# Sheet_MCU_IO.net
KiCad netlist of a schematic drawn in Altium Designer
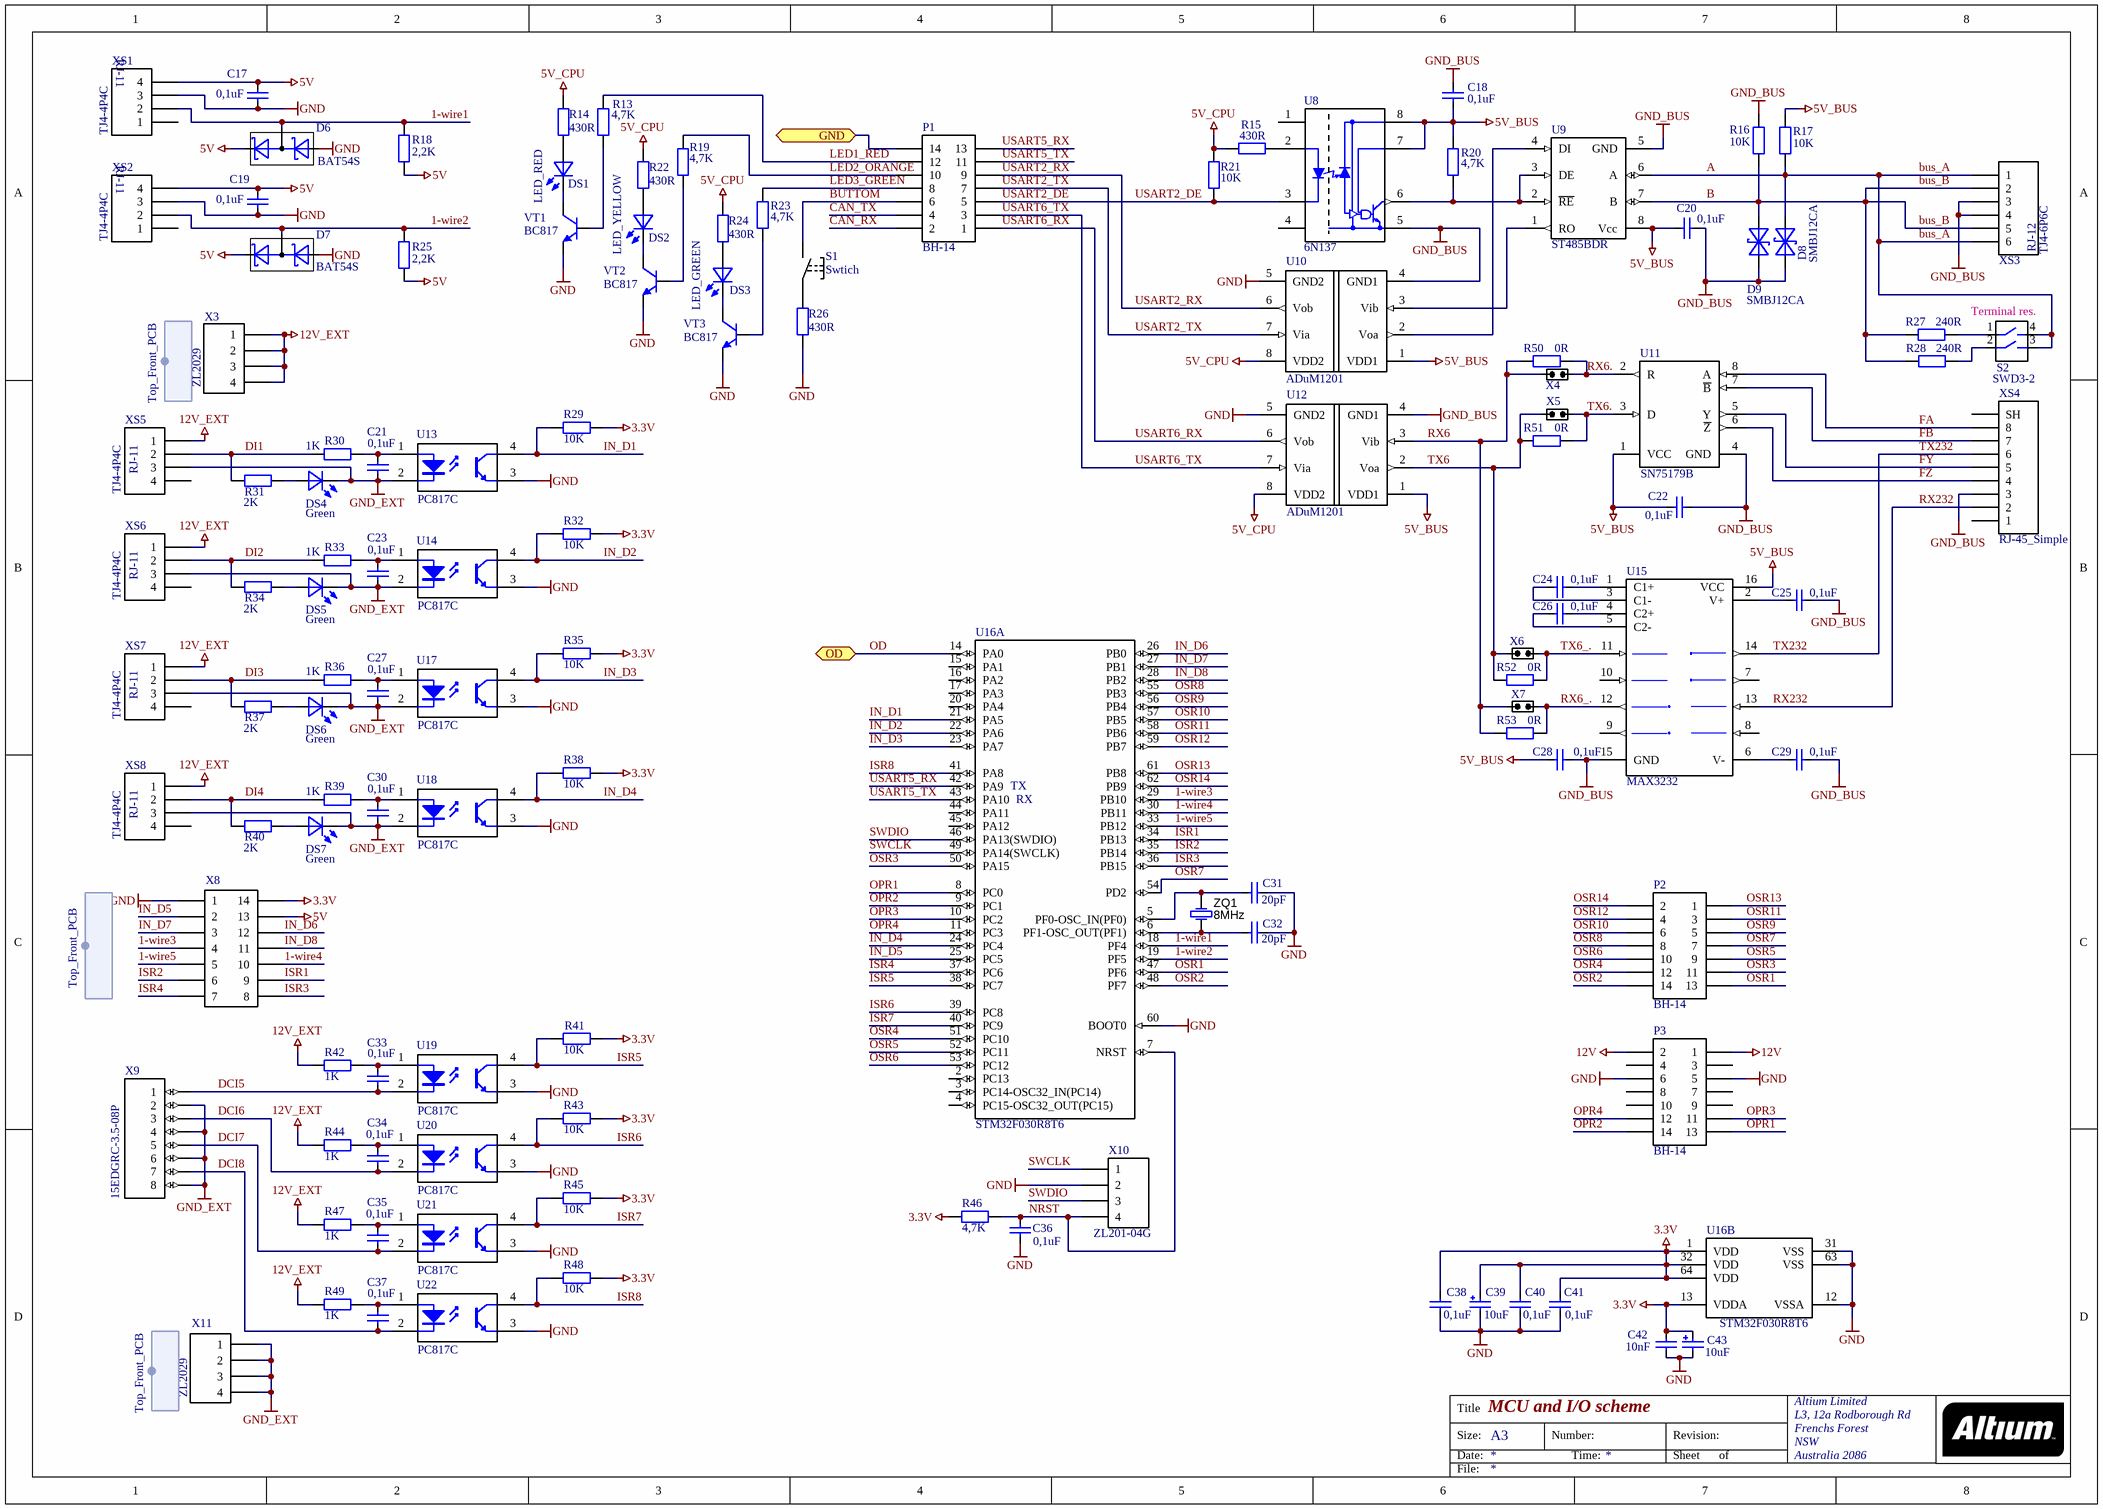
[diagram p0: Sheet_MCU_IO.SchDoc]

(export (version "E")
  (design (tool "Eeschema 10.0.6"))
  (components
    (comp (ref "C17")
      (value "0,1uF")
      (footprint "C_0805")
      (description "Capacitor semi")
      (fields (field (name "Comment") "Cap_Semi"))
      (libsource (lib "Capacitor") (part "Cap_Semi"))
    )
    (comp (ref "C18")
      (value "0,1uF")
      (footprint "C_0805")
      (description "Capacitor semi")
      (fields (field (name "Comment") "Cap_Semi"))
      (libsource (lib "Capacitor") (part "Cap_Semi"))
    )
    (comp (ref "C19")
      (value "0,1uF")
      (footprint "C_0805")
      (description "Capacitor semi")
      (fields (field (name "Comment") "Cap_Semi"))
      (libsource (lib "Capacitor") (part "Cap_Semi"))
    )
    (comp (ref "C20")
      (value "0,1uF")
      (footprint "C_0805")
      (description "Capacitor semi")
      (fields (field (name "Comment") "Cap_Semi"))
      (libsource (lib "Capacitor") (part "Cap_Semi"))
    )
    (comp (ref "C21")
      (value "0,1uF")
      (footprint "C_0805")
      (description "Capacitor semi")
      (fields (field (name "Comment") "Cap_Semi"))
      (libsource (lib "Capacitor") (part "Cap_Semi"))
    )
    (comp (ref "C22")
      (value "0,1uF")
      (footprint "C_0805")
      (description "Capacitor semi")
      (fields (field (name "Comment") "Cap_Semi"))
      (libsource (lib "Capacitor") (part "Cap_Semi"))
    )
    (comp (ref "C23")
      (value "0,1uF")
      (footprint "C_0805")
      (description "Capacitor semi")
      (fields (field (name "Comment") "Cap_Semi"))
      (libsource (lib "Capacitor") (part "Cap_Semi"))
    )
    (comp (ref "C24")
      (value "0,1uF")
      (footprint "C_0805")
      (description "Capacitor semi")
      (fields (field (name "Comment") "Cap_Semi"))
      (libsource (lib "Capacitor") (part "Cap_Semi"))
    )
    (comp (ref "C25")
      (value "0,1uF")
      (footprint "C_0805")
      (description "Capacitor semi")
      (fields (field (name "Comment") "Cap_Semi"))
      (libsource (lib "Capacitor") (part "Cap_Semi"))
    )
    (comp (ref "C26")
      (value "0,1uF")
      (footprint "C_0805")
      (description "Capacitor semi")
      (fields (field (name "Comment") "Cap_Semi"))
      (libsource (lib "Capacitor") (part "Cap_Semi"))
    )
    (comp (ref "C27")
      (value "0,1uF")
      (footprint "C_0805")
      (description "Capacitor semi")
      (fields (field (name "Comment") "Cap_Semi"))
      (libsource (lib "Capacitor") (part "Cap_Semi"))
    )
    (comp (ref "C28")
      (value "0,1uF")
      (footprint "C_0805")
      (description "Capacitor semi")
      (fields (field (name "Comment") "Cap_Semi"))
      (libsource (lib "Capacitor") (part "Cap_Semi"))
    )
    (comp (ref "C29")
      (value "0,1uF")
      (footprint "C_0805")
      (description "Capacitor semi")
      (fields (field (name "Comment") "Cap_Semi"))
      (libsource (lib "Capacitor") (part "Cap_Semi"))
    )
    (comp (ref "C30")
      (value "0,1uF")
      (footprint "C_0805")
      (description "Capacitor semi")
      (fields (field (name "Comment") "Cap_Semi"))
      (libsource (lib "Capacitor") (part "Cap_Semi"))
    )
    (comp (ref "C31")
      (value "20pF")
      (footprint "C_0805")
      (description "Capacitor semi")
      (fields (field (name "Comment") "Cap_Semi"))
      (libsource (lib "Capacitor") (part "Cap_Semi"))
    )
    (comp (ref "C32")
      (value "20pF")
      (footprint "C_0805")
      (description "Capacitor semi")
      (fields (field (name "Comment") "Cap_Semi"))
      (libsource (lib "Capacitor") (part "Cap_Semi"))
    )
    (comp (ref "C33")
      (value "0,1uF")
      (footprint "C_0805")
      (description "Capacitor semi")
      (fields (field (name "Comment") "Cap_Semi"))
      (libsource (lib "Capacitor") (part "Cap_Semi"))
    )
    (comp (ref "C34")
      (value "0,1uF")
      (footprint "C_0805")
      (description "Capacitor semi")
      (fields (field (name "Comment") "Cap_Semi"))
      (libsource (lib "Capacitor") (part "Cap_Semi"))
    )
    (comp (ref "C35")
      (value "0,1uF")
      (footprint "C_0805")
      (description "Capacitor semi")
      (fields (field (name "Comment") "Cap_Semi"))
      (libsource (lib "Capacitor") (part "Cap_Semi"))
    )
    (comp (ref "C36")
      (value "0,1uF")
      (footprint "C_0805")
      (description "Capacitor semi")
      (fields (field (name "Comment") "Cap_Semi"))
      (libsource (lib "Capacitor") (part "Cap_Semi"))
    )
    (comp (ref "C37")
      (value "0,1uF")
      (footprint "C_0805")
      (description "Capacitor semi")
      (fields (field (name "Comment") "Cap_Semi"))
      (libsource (lib "Capacitor") (part "Cap_Semi"))
    )
    (comp (ref "C38")
      (value "0,1uF")
      (footprint "C_0805")
      (description "Capacitor semi")
      (fields (field (name "Comment") "Cap_Semi"))
      (libsource (lib "Capacitor") (part "Cap_Semi"))
    )
    (comp (ref "C39")
      (value "10uF")
      (footprint "5x11")
      (description "Capacitor polar")
      (fields (field (name "Comment") "Cap_Polar"))
      (libsource (lib "Capacitor") (part "Capacitor Polar"))
    )
    (comp (ref "C40")
      (value "0,1uF")
      (footprint "C_0805")
      (description "Capacitor semi")
      (fields (field (name "Comment") "Cap_Semi"))
      (libsource (lib "Capacitor") (part "Cap_Semi"))
    )
    (comp (ref "C41")
      (value "0,1uF")
      (footprint "C_0805")
      (description "Capacitor semi")
      (fields (field (name "Comment") "Cap_Semi"))
      (libsource (lib "Capacitor") (part "Cap_Semi"))
    )
    (comp (ref "C42")
      (value "10nF")
      (footprint "C_0805")
      (description "Capacitor semi")
      (fields (field (name "Comment") "Cap_Semi"))
      (libsource (lib "Capacitor") (part "Cap_Semi"))
    )
    (comp (ref "C43")
      (value "10uF")
      (footprint "5x11")
      (description "Capacitor polar")
      (fields (field (name "Comment") "Cap_Polar"))
      (libsource (lib "Capacitor") (part "Capacitor Polar"))
    )
    (comp (ref "D6")
      (value "BAT54S")
      (footprint "SOT-23_d")
      (description "Diode Schottky")
      (libsource (lib "Diode") (part "BAT54S"))
    )
    (comp (ref "D7")
      (value "BAT54S")
      (footprint "SOT-23_d")
      (description "Diode Schottky")
      (libsource (lib "Diode") (part "BAT54S"))
    )
    (comp (ref "D8")
      (value "SMBJ12CA")
      (footprint "SMB")
      (description "Supressor")
      (libsource (lib "Diode") (part "SMBJ12CA"))
    )
    (comp (ref "D9")
      (value "SMBJ12CA")
      (footprint "SMB")
      (description "Supressor")
      (libsource (lib "Diode") (part "SMBJ12CA"))
    )
    (comp (ref "DS1")
      (value "LED_RED")
      (footprint "LED_RED")
      (description "LED")
      (libsource (lib "LEDs") (part "LED_RED"))
    )
    (comp (ref "DS2")
      (value "LED_YELLOW")
      (footprint "LED_YELLOW")
      (description "LED")
      (libsource (lib "LEDs") (part "LED_YELLOW"))
    )
    (comp (ref "DS3")
      (value "LED_GREEN")
      (footprint "LED_GREEN")
      (description "LED")
      (libsource (lib "LEDs") (part "LED_GREEN"))
    )
    (comp (ref "DS4")
      (value "Green")
      (footprint "LED_SMD_0805")
      (description "LED_SMD")
      (libsource (lib "LEDs") (part "LED"))
    )
    (comp (ref "DS5")
      (value "Green")
      (footprint "LED_SMD_0805")
      (description "LED_SMD")
      (libsource (lib "LEDs") (part "LED"))
    )
    (comp (ref "DS6")
      (value "Green")
      (footprint "LED_SMD_0805")
      (description "LED_SMD")
      (libsource (lib "LEDs") (part "LED"))
    )
    (comp (ref "DS7")
      (value "Green")
      (footprint "LED_SMD_0805")
      (description "LED_SMD")
      (libsource (lib "LEDs") (part "LED"))
    )
    (comp (ref "P1")
      (value "BH-14")
      (footprint "BH-14")
      (description "IDC/BH")
      (fields (field (name "PUBLISHER") "Altium Limited"))
      (libsource (lib "") (part "BH-14_1"))
    )
    (comp (ref "P2")
      (value "BH-14")
      (footprint "BH-14")
      (description "IDC/BH")
      (fields (field (name "PUBLISHER") "Altium Limited"))
      (libsource (lib "Connect") (part "BH-14"))
    )
    (comp (ref "P3")
      (value "BH-14")
      (footprint "BH-14")
      (description "IDC/BH")
      (fields (field (name "PUBLISHER") "Altium Limited"))
      (libsource (lib "Connect") (part "BH-14"))
    )
    (comp (ref "R13")
      (value "4,7K")
      (footprint "R_0805")
      (description "Resistor")
      (libsource (lib "Resistors") (part "Resistor"))
    )
    (comp (ref "R14")
      (value "430R")
      (footprint "R_0805")
      (description "Resistor")
      (libsource (lib "") (part "Resistor_3"))
    )
    (comp (ref "R15")
      (value "430R")
      (footprint "R_0805")
      (description "Resistor")
      (libsource (lib "") (part "Resistor_2"))
    )
    (comp (ref "R16")
      (value "10K")
      (footprint "R_0805")
      (description "Resistor")
      (libsource (lib "Resistors") (part "Resistor"))
    )
    (comp (ref "R17")
      (value "10K")
      (footprint "R_0805")
      (description "Resistor")
      (libsource (lib "Resistors") (part "Resistor"))
    )
    (comp (ref "R18")
      (value "2,2K")
      (footprint "R_0805")
      (description "Resistor")
      (libsource (lib "") (part "Resistor_2"))
    )
    (comp (ref "R19")
      (value "4,7K")
      (footprint "R_0805")
      (description "Resistor")
      (libsource (lib "Resistors") (part "Resistor"))
    )
    (comp (ref "R20")
      (value "4,7K")
      (footprint "R_0805")
      (description "Resistor")
      (libsource (lib "Resistors") (part "Resistor"))
    )
    (comp (ref "R21")
      (value "10K")
      (footprint "R_0805")
      (description "Resistor")
      (libsource (lib "Resistors") (part "Resistor"))
    )
    (comp (ref "R22")
      (value "430R")
      (footprint "R_0805")
      (description "Resistor")
      (libsource (lib "") (part "Resistor_3"))
    )
    (comp (ref "R23")
      (value "4,7K")
      (footprint "R_0805")
      (description "Resistor")
      (libsource (lib "Resistors") (part "Resistor"))
    )
    (comp (ref "R24")
      (value "430R")
      (footprint "R_0805")
      (description "Resistor")
      (libsource (lib "") (part "Resistor_3"))
    )
    (comp (ref "R25")
      (value "2,2K")
      (footprint "R_0805")
      (description "Resistor")
      (libsource (lib "") (part "Resistor_2"))
    )
    (comp (ref "R26")
      (value "430R")
      (footprint "R_0805")
      (description "Resistor")
      (libsource (lib "") (part "Resistor_3"))
    )
    (comp (ref "R27")
      (value "240R")
      (footprint "R_1206")
      (description "Resistor")
      (libsource (lib "") (part "Resistor_1"))
    )
    (comp (ref "R28")
      (value "240R")
      (footprint "R_1206")
      (description "Resistor")
      (libsource (lib "") (part "Resistor_1"))
    )
    (comp (ref "R29")
      (value "10K")
      (footprint "R_0805")
      (description "Resistor")
      (libsource (lib "") (part "Resistor_2"))
    )
    (comp (ref "R30")
      (value "1K")
      (footprint "R_0805")
      (description "Resistor")
      (libsource (lib "") (part "Resistor_2"))
    )
    (comp (ref "R31")
      (value "2K")
      (footprint "R_0805")
      (description "Resistor")
      (libsource (lib "") (part "Resistor_2"))
    )
    (comp (ref "R32")
      (value "10K")
      (footprint "R_0805")
      (description "Resistor")
      (libsource (lib "") (part "Resistor_2"))
    )
    (comp (ref "R33")
      (value "1K")
      (footprint "R_0805")
      (description "Resistor")
      (libsource (lib "") (part "Resistor_2"))
    )
    (comp (ref "R34")
      (value "2K")
      (footprint "R_0805")
      (description "Resistor")
      (libsource (lib "") (part "Resistor_2"))
    )
    (comp (ref "R35")
      (value "10K")
      (footprint "R_0805")
      (description "Resistor")
      (libsource (lib "") (part "Resistor_2"))
    )
    (comp (ref "R36")
      (value "1K")
      (footprint "R_0805")
      (description "Resistor")
      (libsource (lib "") (part "Resistor_2"))
    )
    (comp (ref "R37")
      (value "2K")
      (footprint "R_0805")
      (description "Resistor")
      (libsource (lib "") (part "Resistor_2"))
    )
    (comp (ref "R38")
      (value "10K")
      (footprint "R_0805")
      (description "Resistor")
      (libsource (lib "") (part "Resistor_2"))
    )
    (comp (ref "R39")
      (value "1K")
      (footprint "R_0805")
      (description "Resistor")
      (libsource (lib "") (part "Resistor_2"))
    )
    (comp (ref "R40")
      (value "2K")
      (footprint "R_0805")
      (description "Resistor")
      (libsource (lib "") (part "Resistor_2"))
    )
    (comp (ref "R41")
      (value "10K")
      (footprint "R_0805")
      (description "Resistor")
      (libsource (lib "") (part "Resistor_2"))
    )
    (comp (ref "R42")
      (value "1K")
      (footprint "R_0805")
      (description "Resistor")
      (libsource (lib "") (part "Resistor_2"))
    )
    (comp (ref "R43")
      (value "10K")
      (footprint "R_0805")
      (description "Resistor")
      (libsource (lib "") (part "Resistor_2"))
    )
    (comp (ref "R44")
      (value "1K")
      (footprint "R_0805")
      (description "Resistor")
      (libsource (lib "") (part "Resistor_2"))
    )
    (comp (ref "R45")
      (value "10K")
      (footprint "R_0805")
      (description "Resistor")
      (libsource (lib "") (part "Resistor_2"))
    )
    (comp (ref "R46")
      (value "4,7K")
      (footprint "R_0805")
      (description "Resistor")
      (libsource (lib "") (part "Resistor_1"))
    )
    (comp (ref "R47")
      (value "1K")
      (footprint "R_0805")
      (description "Resistor")
      (libsource (lib "") (part "Resistor_2"))
    )
    (comp (ref "R48")
      (value "10K")
      (footprint "R_0805")
      (description "Resistor")
      (libsource (lib "") (part "Resistor_2"))
    )
    (comp (ref "R49")
      (value "1K")
      (footprint "R_0805")
      (description "Resistor")
      (libsource (lib "") (part "Resistor_2"))
    )
    (comp (ref "R50")
      (value "0R")
      (footprint "R_0805")
      (description "Resistor")
      (libsource (lib "") (part "Resistor_2"))
    )
    (comp (ref "R51")
      (value "0R")
      (footprint "R_0805")
      (description "Resistor")
      (libsource (lib "") (part "Resistor_2"))
    )
    (comp (ref "R52")
      (value "0R")
      (footprint "R_0805")
      (description "Resistor")
      (libsource (lib "") (part "Resistor_2"))
    )
    (comp (ref "R53")
      (value "0R")
      (footprint "R_0805")
      (description "Resistor")
      (libsource (lib "") (part "Resistor_2"))
    )
    (comp (ref "S1")
      (value "Swtich")
      (footprint "Swich_TACTA-68N-F_")
      (libsource (lib "Other") (part "Swtich"))
    )
    (comp (ref "S2")
      (value "SW DIP-2")
      (footprint "Swich_DIP2")
      (description "DIP Switch_2")
      (fields (field (name "ALTIUM_UNNAMED_1") "SWD3-2"))
      (libsource (lib "Other") (part "SW DIP-2"))
    )
    (comp (ref "U8")
      (value "6N137")
      (footprint "DIP-8")
      (description "Optocoupler")
      (libsource (lib "Chip_Packaging") (part "6N137"))
    )
    (comp (ref "U9")
      (value "ST485BDR")
      (footprint "SO-8_N")
      (description "RS-485/RS-422 Transceiver")
      (libsource (lib "Chip_Packaging") (part "ST485BDR"))
    )
    (comp (ref "U10")
      (value "ADuM1201")
      (footprint "SO-8_N")
      (description "Dual-Channel Digital Isolators")
      (libsource (lib "Chip_Packaging") (part "ADuM1201"))
    )
    (comp (ref "U11")
      (value "SN75179B")
      (footprint "SO-8_L")
      (description "RS485/RS422 Differential driver and receiver pair")
      (libsource (lib "Chip_Packaging") (part "SN75179B"))
    )
    (comp (ref "U12")
      (value "ADuM1201")
      (footprint "SO-8_N")
      (description "Dual-Channel Digital Isolators")
      (libsource (lib "Chip_Packaging") (part "ADuM1201"))
    )
    (comp (ref "U13")
      (value "PC817C")
      (footprint "DIP-4")
      (description "Optocoupler")
      (libsource (lib "Chip_Packaging") (part "PC817"))
    )
    (comp (ref "U14")
      (value "PC817C")
      (footprint "DIP-4")
      (description "Optocoupler")
      (libsource (lib "Chip_Packaging") (part "PC817"))
    )
    (comp (ref "U15")
      (value "MAX3232")
      (footprint "SO-16_N")
      (description "RS-232 Transceiver")
      (fields (field (name "PUBLISHER") "Altium Limited"))
      (libsource (lib "Chip_Packaging") (part "MAX3232"))
    )
    (comp (ref "U16")
      (value "STM32F030R8T6")
      (footprint "LQFP64_L")
      (libsource (lib "Chip_Packaging") (part "STM32F030R8T6"))
    )
    (comp (ref "U17")
      (value "PC817C")
      (footprint "DIP-4")
      (description "Optocoupler")
      (libsource (lib "Chip_Packaging") (part "PC817"))
    )
    (comp (ref "U18")
      (value "PC817C")
      (footprint "DIP-4")
      (description "Optocoupler")
      (libsource (lib "Chip_Packaging") (part "PC817"))
    )
    (comp (ref "U19")
      (value "PC817C")
      (footprint "DIP-4")
      (description "Optocoupler")
      (libsource (lib "Chip_Packaging") (part "PC817"))
    )
    (comp (ref "U20")
      (value "PC817C")
      (footprint "DIP-4")
      (description "Optocoupler")
      (libsource (lib "Chip_Packaging") (part "PC817"))
    )
    (comp (ref "U21")
      (value "PC817C")
      (footprint "DIP-4")
      (description "Optocoupler")
      (libsource (lib "Chip_Packaging") (part "PC817"))
    )
    (comp (ref "U22")
      (value "PC817C")
      (footprint "DIP-4")
      (description "Optocoupler")
      (libsource (lib "Chip_Packaging") (part "PC817"))
    )
    (comp (ref "VT1")
      (value "BC817")
      (footprint "SOT-23_N")
      (description "NPN")
      (libsource (lib "Transistors") (part "BC817"))
    )
    (comp (ref "VT2")
      (value "BC817")
      (footprint "SOT-23_N")
      (description "NPN")
      (libsource (lib "Transistors") (part "BC817"))
    )
    (comp (ref "VT3")
      (value "BC817")
      (footprint "SOT-23_N")
      (description "NPN")
      (libsource (lib "Transistors") (part "BC817"))
    )
    (comp (ref "X3")
      (value "ZL2029")
      (footprint "PLS-4-3D")
      (description "Header, 4-Pin")
      (fields (field (name "ALTIUM_UNNAMED_1") "ZL2029") (field (name "PUBLISHER") "Altium Limited"))
      (libsource (lib "Connect") (part "PLS-4"))
    )
    (comp (ref "X4")
      (value "JMP")
      (footprint "PLS-2-2")
      (description "Jumper")
      (fields (field (name "PUBLISHER") "Altium Limited"))
      (libsource (lib "Connect") (part "JMP"))
    )
    (comp (ref "X5")
      (value "JMP")
      (footprint "PLS-2-2")
      (description "Jumper")
      (fields (field (name "PUBLISHER") "Altium Limited"))
      (libsource (lib "Connect") (part "JMP"))
    )
    (comp (ref "X6")
      (value "JMP")
      (footprint "PLS-2-2")
      (description "Jumper")
      (fields (field (name "PUBLISHER") "Altium Limited"))
      (libsource (lib "Connect") (part "JMP"))
    )
    (comp (ref "X7")
      (value "JMP")
      (footprint "PLS-2-2")
      (description "Jumper")
      (fields (field (name "PUBLISHER") "Altium Limited"))
      (libsource (lib "Connect") (part "JMP"))
    )
    (comp (ref "X8")
      (value "PLS2-14")
      (footprint "PLS2-14")
      (description "Header, 14-Pin")
      (libsource (lib "Connect") (part "PLS2-14"))
    )
    (comp (ref "X9")
      (value "15EDGRC-3.5-08P")
      (footprint "MC_3.5_8")
      (description "Connector 3.5mm")
      (libsource (lib "Connect") (part "MC_3.5_8"))
    )
    (comp (ref "X10")
      (value "PLS-4")
      (footprint "PLS-4-3D")
      (description "ZL201-04G")
      (fields (field (name "ALTIUM_UNNAMED_1") "ZL201-04G") (field (name "PUBLISHER") "Altium Limited"))
      (libsource (lib "") (part "PLS-4_1"))
    )
    (comp (ref "X11")
      (value "PLS-4")
      (footprint "PLS-4-3D")
      (description "ZL2029")
      (fields (field (name "ALTIUM_UNNAMED_1") "ZL2029") (field (name "PUBLISHER") "Altium Limited"))
      (libsource (lib "Connect") (part "PLS-4"))
    )
    (comp (ref "XS1")
      (value "RJ-11")
      (footprint "RJ-11 - TJ4-4P4C")
      (description "TJ4-4P4C")
      (fields (field (name "ALTIUM_UNNAMED_1") "TJ4-4P4C"))
      (libsource (lib "Connect") (part "RJ-11"))
    )
    (comp (ref "XS2")
      (value "RJ-11")
      (footprint "RJ-11 - TJ4-4P4C")
      (description "TJ4-4P4C")
      (fields (field (name "ALTIUM_UNNAMED_1") "TJ4-4P4C"))
      (libsource (lib "Connect") (part "RJ-11"))
    )
    (comp (ref "XS3")
      (value "RJ-12")
      (footprint "RJ-12 - TJ4-6P6C")
      (description "TJ4-6P6C")
      (fields (field (name "ALTIUM_UNNAMED_1") "TJ4-6P6C"))
      (libsource (lib "Connect") (part "RJ-12"))
    )
    (comp (ref "XS4")
      (value "RJ-45_Simple")
      (footprint "RJ-45 - TJ4-8P8C")
      (description "Connector RJ-45 Simple")
      (libsource (lib "Connect") (part "RJ-45_Simple"))
    )
    (comp (ref "XS5")
      (value "RJ-11")
      (footprint "RJ-11 - TJ4-4P4C")
      (description "TJ4-4P4C")
      (fields (field (name "ALTIUM_UNNAMED_1") "TJ4-4P4C"))
      (libsource (lib "") (part "RJ-11_1"))
    )
    (comp (ref "XS6")
      (value "RJ-11")
      (footprint "RJ-11 - TJ4-4P4C")
      (description "TJ4-4P4C")
      (fields (field (name "ALTIUM_UNNAMED_1") "TJ4-4P4C"))
      (libsource (lib "") (part "RJ-11_1"))
    )
    (comp (ref "XS7")
      (value "RJ-11")
      (footprint "RJ-11 - TJ4-4P4C")
      (description "TJ4-4P4C")
      (fields (field (name "ALTIUM_UNNAMED_1") "TJ4-4P4C"))
      (libsource (lib "") (part "RJ-11_1"))
    )
    (comp (ref "XS8")
      (value "RJ-11")
      (footprint "RJ-11 - TJ4-4P4C")
      (description "TJ4-4P4C")
      (fields (field (name "ALTIUM_UNNAMED_1") "TJ4-4P4C"))
      (libsource (lib "") (part "RJ-11_1"))
    )
    (comp (ref "ZQ1")
      (value "8MHz")
      (footprint "HC49S_3D")
      (description "Crystal Oscillator")
      (fields (field (name "PUBLISHER") "Altium Limited"))
      (libsource (lib "Oscillator") (part "XTAL"))
    )
  )
  (nets
    (net (code "1") (name "/1-wire1") (class "Default")
      (node (ref "D6") (pin "3") (pinfunction "CA_3") (pintype "passive"))
      (node (ref "R18") (pin "1") (pinfunction "1_1") (pintype "passive"))
      (node (ref "U16") (pin "18") (pinfunction "PF4_18") (pintype "bidirectional"))
      (node (ref "XS1") (pin "2") (pinfunction "2_2") (pintype "passive"))
    )
    (net (code "2") (name "/1-wire2") (class "Default")
      (node (ref "D7") (pin "3") (pinfunction "CA_3") (pintype "passive"))
      (node (ref "R25") (pin "1") (pinfunction "1_1") (pintype "passive"))
      (node (ref "U16") (pin "19") (pinfunction "PF5_19") (pintype "bidirectional"))
      (node (ref "XS2") (pin "2") (pinfunction "2_2") (pintype "passive"))
    )
    (net (code "3") (name "/1-wire3") (class "Default")
      (node (ref "U16") (pin "29") (pinfunction "PB10_29") (pintype "bidirectional"))
      (node (ref "X8") (pin "4") (pinfunction "4_4") (pintype "passive"))
    )
    (net (code "4") (name "/1-wire4") (class "Default")
      (node (ref "U16") (pin "30") (pinfunction "PB11_30") (pintype "bidirectional"))
      (node (ref "X8") (pin "10") (pinfunction "10_10") (pintype "passive"))
    )
    (net (code "5") (name "/1-wire5") (class "Default")
      (node (ref "U16") (pin "33") (pinfunction "PB12_33") (pintype "bidirectional"))
      (node (ref "X8") (pin "5") (pinfunction "5_5") (pintype "passive"))
    )
    (net (code "6") (name "/A") (class "Default")
      (node (ref "D8") (pin "2") (pinfunction "C_2") (pintype "passive"))
      (node (ref "R17") (pin "1") (pinfunction "1_1") (pintype "passive"))
      (node (ref "S2") (pin "3") (pinfunction "3_3") (pintype "passive"))
      (node (ref "S2") (pin "4") (pinfunction "4_4") (pintype "passive"))
      (node (ref "U9") (pin "6") (pinfunction "A_6") (pintype "bidirectional"))
      (node (ref "XS3") (pin "1") (pinfunction "1_1") (pintype "passive"))
      (node (ref "XS3") (pin "6") (pinfunction "6_6") (pintype "passive"))
    )
    (net (code "7") (name "/B") (class "Default")
      (node (ref "D9") (pin "1") (pinfunction "A_1") (pintype "passive"))
      (node (ref "R16") (pin "1") (pinfunction "1_1") (pintype "passive"))
      (node (ref "R27") (pin "1") (pinfunction "1_1") (pintype "passive"))
      (node (ref "R28") (pin "1") (pinfunction "1_1") (pintype "passive"))
      (node (ref "U9") (pin "7") (pinfunction "B_7") (pintype "bidirectional"))
      (node (ref "XS3") (pin "2") (pinfunction "2_2") (pintype "passive"))
      (node (ref "XS3") (pin "5") (pinfunction "5_5") (pintype "passive"))
    )
    (net (code "8") (name "/BUTTOM") (class "Default")
      (node (ref "P1") (pin "6") (pinfunction "6_6") (pintype "passive"))
      (node (ref "S1") (pin "2") (pinfunction "NO_2") (pintype "passive"))
    )
    (net (code "9") (name "/CAN_RX") (class "Default")
      (node (ref "P1") (pin "2") (pinfunction "2_2") (pintype "passive"))
    )
    (net (code "10") (name "/CAN_TX") (class "Default")
      (node (ref "P1") (pin "4") (pinfunction "4_4") (pintype "passive"))
    )
    (net (code "11") (name "/DCI5") (class "Default")
      (node (ref "C33") (pin "2") (pinfunction "2_2") (pintype "passive"))
      (node (ref "U19") (pin "2") (pinfunction "K_2") (pintype "passive"))
      (node (ref "X9") (pin "1") (pinfunction "1_1") (pintype "bidirectional"))
    )
    (net (code "12") (name "/DCI6") (class "Default")
      (node (ref "C34") (pin "2") (pinfunction "2_2") (pintype "passive"))
      (node (ref "U20") (pin "2") (pinfunction "K_2") (pintype "passive"))
      (node (ref "X9") (pin "3") (pinfunction "3_3") (pintype "bidirectional"))
    )
    (net (code "13") (name "/DCI7") (class "Default")
      (node (ref "C35") (pin "2") (pinfunction "2_2") (pintype "passive"))
      (node (ref "U21") (pin "2") (pinfunction "K_2") (pintype "passive"))
      (node (ref "X9") (pin "5") (pinfunction "5_5") (pintype "bidirectional"))
    )
    (net (code "14") (name "/DCI8") (class "Default")
      (node (ref "C37") (pin "2") (pinfunction "2_2") (pintype "passive"))
      (node (ref "U22") (pin "2") (pinfunction "K_2") (pintype "passive"))
      (node (ref "X9") (pin "7") (pinfunction "7_7") (pintype "bidirectional"))
    )
    (net (code "15") (name "/DI1") (class "Default")
      (node (ref "R30") (pin "2") (pinfunction "2_2") (pintype "passive"))
      (node (ref "R31") (pin "2") (pinfunction "2_2") (pintype "passive"))
      (node (ref "XS5") (pin "2") (pinfunction "2_2") (pintype "passive"))
    )
    (net (code "16") (name "/DI2") (class "Default")
      (node (ref "R33") (pin "2") (pinfunction "2_2") (pintype "passive"))
      (node (ref "R34") (pin "2") (pinfunction "2_2") (pintype "passive"))
      (node (ref "XS6") (pin "2") (pinfunction "2_2") (pintype "passive"))
    )
    (net (code "17") (name "/DI3") (class "Default")
      (node (ref "R36") (pin "2") (pinfunction "2_2") (pintype "passive"))
      (node (ref "R37") (pin "2") (pinfunction "2_2") (pintype "passive"))
      (node (ref "XS7") (pin "2") (pinfunction "2_2") (pintype "passive"))
    )
    (net (code "18") (name "/DI4") (class "Default")
      (node (ref "R39") (pin "2") (pinfunction "2_2") (pintype "passive"))
      (node (ref "R40") (pin "2") (pinfunction "2_2") (pintype "passive"))
      (node (ref "XS8") (pin "2") (pinfunction "2_2") (pintype "passive"))
    )
    (net (code "19") (name "/FA") (class "Default")
      (node (ref "U11") (pin "8") (pinfunction "A_8") (pintype "input"))
      (node (ref "XS4") (pin "8") (pinfunction "8_8") (pintype "passive"))
    )
    (net (code "20") (name "/FY") (class "Default")
      (node (ref "U11") (pin "5") (pinfunction "Y_5") (pintype "output"))
      (node (ref "XS4") (pin "5") (pinfunction "5_5") (pintype "passive"))
    )
    (net (code "21") (name "/F~{B}") (class "Default")
      (node (ref "U11") (pin "7") (pinfunction "~{B}_7") (pintype "input"))
      (node (ref "XS4") (pin "7") (pinfunction "7_7") (pintype "passive"))
    )
    (net (code "22") (name "/F~{Z}") (class "Default")
      (node (ref "U11") (pin "6") (pinfunction "~{Z}_6") (pintype "output"))
      (node (ref "XS4") (pin "4") (pinfunction "4_4") (pintype "passive"))
    )
    (net (code "23") (name "/IN_D1") (class "Default")
      (node (ref "R29") (pin "2") (pinfunction "2_2") (pintype "passive"))
      (node (ref "U13") (pin "4") (pinfunction "C_4") (pintype "passive"))
      (node (ref "U16") (pin "21") (pinfunction "PA5_21") (pintype "bidirectional"))
    )
    (net (code "24") (name "/IN_D2") (class "Default")
      (node (ref "R32") (pin "2") (pinfunction "2_2") (pintype "passive"))
      (node (ref "U14") (pin "4") (pinfunction "C_4") (pintype "passive"))
      (node (ref "U16") (pin "22") (pinfunction "PA6_22") (pintype "bidirectional"))
    )
    (net (code "25") (name "/IN_D3") (class "Default")
      (node (ref "R35") (pin "2") (pinfunction "2_2") (pintype "passive"))
      (node (ref "U16") (pin "23") (pinfunction "PA7_23") (pintype "bidirectional"))
      (node (ref "U17") (pin "4") (pinfunction "C_4") (pintype "passive"))
    )
    (net (code "26") (name "/IN_D4") (class "Default")
      (node (ref "R38") (pin "2") (pinfunction "2_2") (pintype "passive"))
      (node (ref "U16") (pin "24") (pinfunction "PC4_24") (pintype "bidirectional"))
      (node (ref "U18") (pin "4") (pinfunction "C_4") (pintype "passive"))
    )
    (net (code "27") (name "/IN_D5") (class "Default")
      (node (ref "U16") (pin "25") (pinfunction "PC5_25") (pintype "bidirectional"))
      (node (ref "X8") (pin "2") (pinfunction "2_2") (pintype "passive"))
    )
    (net (code "28") (name "/IN_D6") (class "Default")
      (node (ref "U16") (pin "26") (pinfunction "PB0_26") (pintype "bidirectional"))
      (node (ref "X8") (pin "12") (pinfunction "12_12") (pintype "passive"))
    )
    (net (code "29") (name "/IN_D7") (class "Default")
      (node (ref "U16") (pin "27") (pinfunction "PB1_27") (pintype "bidirectional"))
      (node (ref "X8") (pin "3") (pinfunction "3_3") (pintype "passive"))
    )
    (net (code "30") (name "/IN_D8") (class "Default")
      (node (ref "U16") (pin "28") (pinfunction "PB2_28") (pintype "bidirectional"))
      (node (ref "X8") (pin "11") (pinfunction "11_11") (pintype "passive"))
    )
    (net (code "31") (name "/ISR1") (class "Default")
      (node (ref "U16") (pin "34") (pinfunction "PB13_34") (pintype "bidirectional"))
      (node (ref "X8") (pin "9") (pinfunction "9_9") (pintype "passive"))
    )
    (net (code "32") (name "/ISR2") (class "Default")
      (node (ref "U16") (pin "35") (pinfunction "PB14_35") (pintype "bidirectional"))
      (node (ref "X8") (pin "6") (pinfunction "6_6") (pintype "passive"))
    )
    (net (code "33") (name "/ISR3") (class "Default")
      (node (ref "U16") (pin "36") (pinfunction "PB15_36") (pintype "bidirectional"))
      (node (ref "X8") (pin "8") (pinfunction "8_8") (pintype "passive"))
    )
    (net (code "34") (name "/ISR4") (class "Default")
      (node (ref "U16") (pin "37") (pinfunction "PC6_37") (pintype "bidirectional"))
      (node (ref "X8") (pin "7") (pinfunction "7_7") (pintype "passive"))
    )
    (net (code "35") (name "/ISR5") (class "Default")
      (node (ref "R41") (pin "2") (pinfunction "2_2") (pintype "passive"))
      (node (ref "U16") (pin "38") (pinfunction "PC7_38") (pintype "bidirectional"))
      (node (ref "U19") (pin "4") (pinfunction "C_4") (pintype "passive"))
    )
    (net (code "36") (name "/ISR6") (class "Default")
      (node (ref "R43") (pin "2") (pinfunction "2_2") (pintype "passive"))
      (node (ref "U16") (pin "39") (pinfunction "PC8_39") (pintype "bidirectional"))
      (node (ref "U20") (pin "4") (pinfunction "C_4") (pintype "passive"))
    )
    (net (code "37") (name "/ISR7") (class "Default")
      (node (ref "R45") (pin "2") (pinfunction "2_2") (pintype "passive"))
      (node (ref "U16") (pin "40") (pinfunction "PC9_40") (pintype "bidirectional"))
      (node (ref "U21") (pin "4") (pinfunction "C_4") (pintype "passive"))
    )
    (net (code "38") (name "/ISR8") (class "Default")
      (node (ref "R48") (pin "2") (pinfunction "2_2") (pintype "passive"))
      (node (ref "U16") (pin "41") (pinfunction "PA8_41") (pintype "bidirectional"))
      (node (ref "U22") (pin "4") (pinfunction "C_4") (pintype "passive"))
    )
    (net (code "39") (name "/LED1_RED") (class "Default")
      (node (ref "P1") (pin "12") (pinfunction "12_12") (pintype "passive"))
      (node (ref "R13") (pin "2") (pinfunction "2_2") (pintype "passive"))
    )
    (net (code "40") (name "/LED2_ORANGE") (class "Default")
      (node (ref "P1") (pin "10") (pinfunction "10_10") (pintype "passive"))
      (node (ref "R19") (pin "2") (pinfunction "2_2") (pintype "passive"))
    )
    (net (code "41") (name "/LED3_GREEN") (class "Default")
      (node (ref "P1") (pin "8") (pinfunction "8_8") (pintype "passive"))
      (node (ref "R23") (pin "2") (pinfunction "2_2") (pintype "passive"))
    )
    (net (code "42") (name "/NRST") (class "Default")
      (node (ref "C36") (pin "1") (pinfunction "1_1") (pintype "passive"))
      (node (ref "R46") (pin "2") (pinfunction "2_2") (pintype "passive"))
      (node (ref "U16") (pin "7") (pinfunction "NRST_7") (pintype "bidirectional"))
      (node (ref "X10") (pin "4") (pinfunction "4_4") (pintype "passive"))
    )
    (net (code "43") (name "/OD") (class "Default")
      (node (ref "U16") (pin "14") (pinfunction "PA0_14") (pintype "bidirectional"))
    )
    (net (code "44") (name "/OPR1") (class "Default")
      (node (ref "P3") (pin "13") (pinfunction "13_13") (pintype "passive"))
      (node (ref "U16") (pin "8") (pinfunction "PC0_8") (pintype "bidirectional"))
    )
    (net (code "45") (name "/OPR2") (class "Default")
      (node (ref "P3") (pin "14") (pinfunction "14_14") (pintype "passive"))
      (node (ref "U16") (pin "9") (pinfunction "PC1_9") (pintype "bidirectional"))
    )
    (net (code "46") (name "/OPR3") (class "Default")
      (node (ref "P3") (pin "11") (pinfunction "11_11") (pintype "passive"))
      (node (ref "U16") (pin "10") (pinfunction "PC2_10") (pintype "bidirectional"))
    )
    (net (code "47") (name "/OPR4") (class "Default")
      (node (ref "P3") (pin "12") (pinfunction "12_12") (pintype "passive"))
      (node (ref "U16") (pin "11") (pinfunction "PC3_11") (pintype "bidirectional"))
    )
    (net (code "48") (name "/OSR1") (class "Default")
      (node (ref "P2") (pin "13") (pinfunction "13_13") (pintype "passive"))
      (node (ref "U16") (pin "47") (pinfunction "PF6_47") (pintype "bidirectional"))
    )
    (net (code "49") (name "/OSR2") (class "Default")
      (node (ref "P2") (pin "14") (pinfunction "14_14") (pintype "passive"))
      (node (ref "U16") (pin "48") (pinfunction "PF7_48") (pintype "bidirectional"))
    )
    (net (code "50") (name "/OSR3") (class "Default")
      (node (ref "P2") (pin "11") (pinfunction "11_11") (pintype "passive"))
      (node (ref "U16") (pin "50") (pinfunction "PA15_50") (pintype "bidirectional"))
    )
    (net (code "51") (name "/OSR4") (class "Default")
      (node (ref "P2") (pin "12") (pinfunction "12_12") (pintype "passive"))
      (node (ref "U16") (pin "51") (pinfunction "PC10_51") (pintype "bidirectional"))
    )
    (net (code "52") (name "/OSR5") (class "Default")
      (node (ref "P2") (pin "9") (pinfunction "9_9") (pintype "passive"))
      (node (ref "U16") (pin "52") (pinfunction "PC11_52") (pintype "bidirectional"))
    )
    (net (code "53") (name "/OSR6") (class "Default")
      (node (ref "P2") (pin "10") (pinfunction "10_10") (pintype "passive"))
      (node (ref "U16") (pin "53") (pinfunction "PC12_53") (pintype "bidirectional"))
    )
    (net (code "54") (name "/OSR7") (class "Default")
      (node (ref "P2") (pin "7") (pinfunction "7_7") (pintype "passive"))
      (node (ref "U16") (pin "54") (pinfunction "PD2_54") (pintype "bidirectional"))
    )
    (net (code "55") (name "/OSR8") (class "Default")
      (node (ref "P2") (pin "8") (pinfunction "8_8") (pintype "passive"))
      (node (ref "U16") (pin "55") (pinfunction "PB3_55") (pintype "bidirectional"))
    )
    (net (code "56") (name "/OSR9") (class "Default")
      (node (ref "P2") (pin "5") (pinfunction "5_5") (pintype "passive"))
      (node (ref "U16") (pin "56") (pinfunction "PB4_56") (pintype "bidirectional"))
    )
    (net (code "57") (name "/OSR10") (class "Default")
      (node (ref "P2") (pin "6") (pinfunction "6_6") (pintype "passive"))
      (node (ref "U16") (pin "57") (pinfunction "PB5_57") (pintype "bidirectional"))
    )
    (net (code "58") (name "/OSR11") (class "Default")
      (node (ref "P2") (pin "3") (pinfunction "3_3") (pintype "passive"))
      (node (ref "U16") (pin "58") (pinfunction "PB6_58") (pintype "bidirectional"))
    )
    (net (code "59") (name "/OSR12") (class "Default")
      (node (ref "P2") (pin "4") (pinfunction "4_4") (pintype "passive"))
      (node (ref "U16") (pin "59") (pinfunction "PB7_59") (pintype "bidirectional"))
    )
    (net (code "60") (name "/OSR13") (class "Default")
      (node (ref "P2") (pin "1") (pinfunction "1_1") (pintype "passive"))
      (node (ref "U16") (pin "61") (pinfunction "PB8_61") (pintype "bidirectional"))
    )
    (net (code "61") (name "/OSR14") (class "Default")
      (node (ref "P2") (pin "2") (pinfunction "2_2") (pintype "passive"))
      (node (ref "U16") (pin "62") (pinfunction "PB9_62") (pintype "bidirectional"))
    )
    (net (code "62") (name "/RX6") (class "Default")
      (node (ref "R50") (pin "2") (pinfunction "2_2") (pintype "passive"))
      (node (ref "R53") (pin "2") (pinfunction "2_2") (pintype "passive"))
      (node (ref "U12") (pin "3") (pinfunction "Vib_3") (pintype "input"))
      (node (ref "X4") (pin "1") (pinfunction "1_1") (pintype "passive"))
      (node (ref "X7") (pin "1") (pinfunction "1_1") (pintype "passive"))
    )
    (net (code "63") (name "/RX6.") (class "Default")
      (node (ref "R50") (pin "1") (pinfunction "1_1") (pintype "passive"))
      (node (ref "U11") (pin "2") (pinfunction "R_2") (pintype "output"))
      (node (ref "X4") (pin "2") (pinfunction "2_2") (pintype "passive"))
    )
    (net (code "64") (name "/RX6_.") (class "Default")
      (node (ref "R53") (pin "1") (pinfunction "1_1") (pintype "passive"))
      (node (ref "U15") (pin "12") (pinfunction "R1OUT_12") (pintype "output"))
      (node (ref "X7") (pin "2") (pinfunction "2_2") (pintype "passive"))
    )
    (net (code "65") (name "/RX232") (class "Default")
      (node (ref "U15") (pin "13") (pinfunction "R1IN_13") (pintype "input"))
      (node (ref "XS4") (pin "2") (pinfunction "2_2") (pintype "passive"))
    )
    (net (code "66") (name "/SWCLK") (class "Default")
      (node (ref "U16") (pin "49") (pinfunction "PA14(SWCLK)_49") (pintype "bidirectional"))
      (node (ref "X10") (pin "1") (pinfunction "1_1") (pintype "passive"))
    )
    (net (code "67") (name "/SWDIO") (class "Default")
      (node (ref "U16") (pin "46") (pinfunction "PA13(SWDIO)_46") (pintype "bidirectional"))
      (node (ref "X10") (pin "3") (pinfunction "3_3") (pintype "passive"))
    )
    (net (code "68") (name "/TX6") (class "Default")
      (node (ref "R51") (pin "2") (pinfunction "2_2") (pintype "passive"))
      (node (ref "R52") (pin "2") (pinfunction "2_2") (pintype "passive"))
      (node (ref "U12") (pin "2") (pinfunction "Voa_2") (pintype "output"))
      (node (ref "X5") (pin "1") (pinfunction "1_1") (pintype "passive"))
      (node (ref "X6") (pin "1") (pinfunction "1_1") (pintype "passive"))
    )
    (net (code "69") (name "/TX6.") (class "Default")
      (node (ref "R51") (pin "1") (pinfunction "1_1") (pintype "passive"))
      (node (ref "U11") (pin "3") (pinfunction "D_3") (pintype "input"))
      (node (ref "X5") (pin "2") (pinfunction "2_2") (pintype "passive"))
    )
    (net (code "70") (name "/TX6_.") (class "Default")
      (node (ref "R52") (pin "1") (pinfunction "1_1") (pintype "passive"))
      (node (ref "U15") (pin "11") (pinfunction "T1IN_11") (pintype "input"))
      (node (ref "X6") (pin "2") (pinfunction "2_2") (pintype "passive"))
    )
    (net (code "71") (name "/TX232") (class "Default")
      (node (ref "U15") (pin "14") (pinfunction "T1OUT_14") (pintype "output"))
      (node (ref "XS4") (pin "6") (pinfunction "6_6") (pintype "passive"))
    )
    (net (code "72") (name "/USART2_DE") (class "Default")
      (node (ref "P1") (pin "5") (pinfunction "5_5") (pintype "passive"))
      (node (ref "R21") (pin "1") (pinfunction "1_1") (pintype "passive"))
      (node (ref "U8") (pin "3") (pinfunction "C_3") (pintype "passive"))
    )
    (net (code "73") (name "/USART2_RX") (class "Default")
      (node (ref "P1") (pin "9") (pinfunction "9_9") (pintype "passive"))
      (node (ref "U10") (pin "6") (pinfunction "Vob_6") (pintype "output"))
    )
    (net (code "74") (name "/USART2_TX") (class "Default")
      (node (ref "P1") (pin "7") (pinfunction "7_7") (pintype "passive"))
      (node (ref "U10") (pin "7") (pinfunction "Via_7") (pintype "input"))
    )
    (net (code "75") (name "/USART5_RX") (class "Default")
      (node (ref "P1") (pin "13") (pinfunction "13_13") (pintype "passive"))
      (node (ref "U16") (pin "42") (pinfunction "PA9_42") (pintype "bidirectional"))
    )
    (net (code "76") (name "/USART5_TX") (class "Default")
      (node (ref "P1") (pin "11") (pinfunction "11_11") (pintype "passive"))
      (node (ref "U16") (pin "43") (pinfunction "PA10_43") (pintype "bidirectional"))
    )
    (net (code "77") (name "/USART6_RX") (class "Default")
      (node (ref "P1") (pin "1") (pinfunction "1_1") (pintype "passive"))
      (node (ref "U12") (pin "6") (pinfunction "Vob_6") (pintype "output"))
    )
    (net (code "78") (name "/USART6_TX") (class "Default")
      (node (ref "P1") (pin "3") (pinfunction "3_3") (pintype "passive"))
      (node (ref "U12") (pin "7") (pinfunction "Via_7") (pintype "input"))
    )
    (net (code "79") (name "3.3V") (class "Default")
      (node (ref "C38") (pin "1") (pinfunction "1_1") (pintype "passive"))
      (node (ref "C39") (pin "1") (pinfunction "1_1") (pintype "passive"))
      (node (ref "C40") (pin "1") (pinfunction "1_1") (pintype "passive"))
      (node (ref "C41") (pin "1") (pinfunction "1_1") (pintype "passive"))
      (node (ref "C42") (pin "1") (pinfunction "1_1") (pintype "passive"))
      (node (ref "C43") (pin "1") (pinfunction "1_1") (pintype "passive"))
      (node (ref "R29") (pin "1") (pinfunction "1_1") (pintype "passive"))
      (node (ref "R32") (pin "1") (pinfunction "1_1") (pintype "passive"))
      (node (ref "R35") (pin "1") (pinfunction "1_1") (pintype "passive"))
      (node (ref "R38") (pin "1") (pinfunction "1_1") (pintype "passive"))
      (node (ref "R41") (pin "1") (pinfunction "1_1") (pintype "passive"))
      (node (ref "R43") (pin "1") (pinfunction "1_1") (pintype "passive"))
      (node (ref "R45") (pin "1") (pinfunction "1_1") (pintype "passive"))
      (node (ref "R46") (pin "1") (pinfunction "1_1") (pintype "passive"))
      (node (ref "R48") (pin "1") (pinfunction "1_1") (pintype "passive"))
      (node (ref "U16") (pin "1") (pinfunction "VDD_1") (pintype "power_in"))
      (node (ref "U16") (pin "13") (pinfunction "VDDA_13") (pintype "power_in"))
      (node (ref "U16") (pin "32") (pinfunction "VDD_32") (pintype "power_in"))
      (node (ref "U16") (pin "64") (pinfunction "VDD_64") (pintype "power_in"))
      (node (ref "X8") (pin "14") (pinfunction "14_14") (pintype "passive"))
    )
    (net (code "80") (name "5V") (class "Default")
      (node (ref "C17") (pin "1") (pinfunction "1_1") (pintype "passive"))
      (node (ref "C19") (pin "1") (pinfunction "1_1") (pintype "passive"))
      (node (ref "D6") (pin "2") (pinfunction "C_2") (pintype "passive"))
      (node (ref "D7") (pin "2") (pinfunction "C_2") (pintype "passive"))
      (node (ref "R18") (pin "2") (pinfunction "2_2") (pintype "passive"))
      (node (ref "R25") (pin "2") (pinfunction "2_2") (pintype "passive"))
      (node (ref "X8") (pin "13") (pinfunction "13_13") (pintype "passive"))
      (node (ref "XS1") (pin "4") (pinfunction "4_4") (pintype "passive"))
      (node (ref "XS2") (pin "4") (pinfunction "4_4") (pintype "passive"))
    )
    (net (code "81") (name "5V_BUS") (class "Default")
      (node (ref "C18") (pin "1") (pinfunction "1_1") (pintype "passive"))
      (node (ref "C20") (pin "2") (pinfunction "2_2") (pintype "passive"))
      (node (ref "C22") (pin "2") (pinfunction "2_2") (pintype "passive"))
      (node (ref "C28") (pin "2") (pinfunction "2_2") (pintype "passive"))
      (node (ref "R17") (pin "2") (pinfunction "2_2") (pintype "passive"))
      (node (ref "R20") (pin "2") (pinfunction "2_2") (pintype "passive"))
      (node (ref "U10") (pin "1") (pinfunction "VDD1_1") (pintype "power_in"))
      (node (ref "U11") (pin "1") (pinfunction "VCC_1") (pintype "power_in"))
      (node (ref "U12") (pin "1") (pinfunction "VDD1_1") (pintype "power_in"))
      (node (ref "U15") (pin "16") (pinfunction "VCC_16") (pintype "power_in"))
      (node (ref "U8") (pin "7") (pinfunction "Ve_7") (pintype "passive"))
      (node (ref "U8") (pin "8") (pinfunction "Vcc_8") (pintype "power_in"))
      (node (ref "U9") (pin "8") (pinfunction "Vcc_8") (pintype "power_in"))
    )
    (net (code "82") (name "5V_CPU") (class "Default")
      (node (ref "R14") (pin "1") (pinfunction "1_1") (pintype "passive"))
      (node (ref "R15") (pin "2") (pinfunction "2_2") (pintype "passive"))
      (node (ref "R21") (pin "2") (pinfunction "2_2") (pintype "passive"))
      (node (ref "R22") (pin "1") (pinfunction "1_1") (pintype "passive"))
      (node (ref "R24") (pin "1") (pinfunction "1_1") (pintype "passive"))
      (node (ref "U10") (pin "8") (pinfunction "VDD2_8") (pintype "power_in"))
      (node (ref "U12") (pin "8") (pinfunction "VDD2_8") (pintype "power_in"))
    )
    (net (code "83") (name "12V") (class "Default")
      (node (ref "P3") (pin "1") (pinfunction "1_1") (pintype "passive"))
      (node (ref "P3") (pin "2") (pinfunction "2_2") (pintype "passive"))
    )
    (net (code "84") (name "12V_EXT") (class "Default")
      (node (ref "R42") (pin "2") (pinfunction "2_2") (pintype "passive"))
      (node (ref "R44") (pin "2") (pinfunction "2_2") (pintype "passive"))
      (node (ref "R47") (pin "2") (pinfunction "2_2") (pintype "passive"))
      (node (ref "R49") (pin "2") (pinfunction "2_2") (pintype "passive"))
      (node (ref "X3") (pin "1") (pinfunction "1_1") (pintype "passive"))
      (node (ref "X3") (pin "2") (pinfunction "2_2") (pintype "passive"))
      (node (ref "X3") (pin "3") (pinfunction "3_3") (pintype "passive"))
      (node (ref "X3") (pin "4") (pinfunction "4_4") (pintype "passive"))
      (node (ref "XS5") (pin "1") (pinfunction "1_1") (pintype "passive"))
      (node (ref "XS6") (pin "1") (pinfunction "1_1") (pintype "passive"))
      (node (ref "XS7") (pin "1") (pinfunction "1_1") (pintype "passive"))
      (node (ref "XS8") (pin "1") (pinfunction "1_1") (pintype "passive"))
    )
    (net (code "85") (name "GND") (class "Default")
      (node (ref "C17") (pin "2") (pinfunction "2_2") (pintype "passive"))
      (node (ref "C19") (pin "2") (pinfunction "2_2") (pintype "passive"))
      (node (ref "C31") (pin "1") (pinfunction "1_1") (pintype "passive"))
      (node (ref "C32") (pin "1") (pinfunction "1_1") (pintype "passive"))
      (node (ref "C36") (pin "2") (pinfunction "2_2") (pintype "passive"))
      (node (ref "C38") (pin "2") (pinfunction "2_2") (pintype "passive"))
      (node (ref "C39") (pin "2") (pinfunction "2_2") (pintype "passive"))
      (node (ref "C40") (pin "2") (pinfunction "2_2") (pintype "passive"))
      (node (ref "C41") (pin "2") (pinfunction "2_2") (pintype "passive"))
      (node (ref "C42") (pin "2") (pinfunction "2_2") (pintype "passive"))
      (node (ref "C43") (pin "2") (pinfunction "2_2") (pintype "passive"))
      (node (ref "D6") (pin "1") (pinfunction "A_1") (pintype "passive"))
      (node (ref "D7") (pin "1") (pinfunction "A_1") (pintype "passive"))
      (node (ref "P1") (pin "14") (pinfunction "14_14") (pintype "passive"))
      (node (ref "P3") (pin "5") (pinfunction "5_5") (pintype "passive"))
      (node (ref "P3") (pin "6") (pinfunction "6_6") (pintype "passive"))
      (node (ref "R26") (pin "2") (pinfunction "2_2") (pintype "passive"))
      (node (ref "U10") (pin "5") (pinfunction "GND2_5") (pintype "power_in"))
      (node (ref "U12") (pin "5") (pinfunction "GND2_5") (pintype "power_in"))
      (node (ref "U13") (pin "3") (pinfunction "E_3") (pintype "passive"))
      (node (ref "U14") (pin "3") (pinfunction "E_3") (pintype "passive"))
      (node (ref "U16") (pin "12") (pinfunction "VSSA_12") (pintype "power_in"))
      (node (ref "U16") (pin "31") (pinfunction "VSS_31") (pintype "power_in"))
      (node (ref "U16") (pin "60") (pinfunction "BOOT0_60") (pintype "input"))
      (node (ref "U16") (pin "63") (pinfunction "VSS_63") (pintype "power_in"))
      (node (ref "U17") (pin "3") (pinfunction "E_3") (pintype "passive"))
      (node (ref "U18") (pin "3") (pinfunction "E_3") (pintype "passive"))
      (node (ref "U19") (pin "3") (pinfunction "E_3") (pintype "passive"))
      (node (ref "U20") (pin "3") (pinfunction "E_3") (pintype "passive"))
      (node (ref "U21") (pin "3") (pinfunction "E_3") (pintype "passive"))
      (node (ref "U22") (pin "3") (pinfunction "E_3") (pintype "passive"))
      (node (ref "VT1") (pin "2") (pinfunction "E_2") (pintype "passive"))
      (node (ref "VT2") (pin "2") (pinfunction "E_2") (pintype "passive"))
      (node (ref "VT3") (pin "2") (pinfunction "E_2") (pintype "passive"))
      (node (ref "X10") (pin "2") (pinfunction "2_2") (pintype "passive"))
      (node (ref "X8") (pin "1") (pinfunction "1_1") (pintype "passive"))
      (node (ref "XS1") (pin "3") (pinfunction "3_3") (pintype "passive"))
      (node (ref "XS2") (pin "3") (pinfunction "3_3") (pintype "passive"))
    )
    (net (code "86") (name "GND_BUS") (class "Default")
      (node (ref "C18") (pin "2") (pinfunction "2_2") (pintype "passive"))
      (node (ref "C20") (pin "1") (pinfunction "1_1") (pintype "passive"))
      (node (ref "C22") (pin "1") (pinfunction "1_1") (pintype "passive"))
      (node (ref "C25") (pin "1") (pinfunction "1_1") (pintype "passive"))
      (node (ref "C28") (pin "1") (pinfunction "1_1") (pintype "passive"))
      (node (ref "C29") (pin "1") (pinfunction "1_1") (pintype "passive"))
      (node (ref "D8") (pin "1") (pinfunction "A_1") (pintype "passive"))
      (node (ref "D9") (pin "2") (pinfunction "C_2") (pintype "passive"))
      (node (ref "R16") (pin "2") (pinfunction "2_2") (pintype "passive"))
      (node (ref "U10") (pin "4") (pinfunction "GND1_4") (pintype "power_in"))
      (node (ref "U11") (pin "4") (pinfunction "GND_4") (pintype "power_in"))
      (node (ref "U12") (pin "4") (pinfunction "GND1_4") (pintype "power_in"))
      (node (ref "U15") (pin "15") (pinfunction "GND_15") (pintype "power_in"))
      (node (ref "U8") (pin "5") (pinfunction "GND_5") (pintype "power_in"))
      (node (ref "U9") (pin "5") (pinfunction "GND_5") (pintype "power_in"))
      (node (ref "XS3") (pin "3") (pinfunction "3_3") (pintype "passive"))
      (node (ref "XS3") (pin "4") (pinfunction "4_4") (pintype "passive"))
      (node (ref "XS4") (pin "3") (pinfunction "3_3") (pintype "passive"))
    )
    (net (code "87") (name "GND_EXT") (class "Default")
      (node (ref "C21") (pin "2") (pinfunction "2_2") (pintype "passive"))
      (node (ref "C23") (pin "2") (pinfunction "2_2") (pintype "passive"))
      (node (ref "C27") (pin "2") (pinfunction "2_2") (pintype "passive"))
      (node (ref "C30") (pin "2") (pinfunction "2_2") (pintype "passive"))
      (node (ref "DS4") (pin "2") (pinfunction "C_2") (pintype "passive"))
      (node (ref "DS5") (pin "2") (pinfunction "C_2") (pintype "passive"))
      (node (ref "DS6") (pin "2") (pinfunction "C_2") (pintype "passive"))
      (node (ref "DS7") (pin "2") (pinfunction "C_2") (pintype "passive"))
      (node (ref "U13") (pin "2") (pinfunction "K_2") (pintype "passive"))
      (node (ref "U14") (pin "2") (pinfunction "K_2") (pintype "passive"))
      (node (ref "U17") (pin "2") (pinfunction "K_2") (pintype "passive"))
      (node (ref "U18") (pin "2") (pinfunction "K_2") (pintype "passive"))
      (node (ref "X11") (pin "1") (pinfunction "1_1") (pintype "passive"))
      (node (ref "X11") (pin "2") (pinfunction "2_2") (pintype "passive"))
      (node (ref "X11") (pin "3") (pinfunction "3_3") (pintype "passive"))
      (node (ref "X11") (pin "4") (pinfunction "4_4") (pintype "passive"))
      (node (ref "X9") (pin "2") (pinfunction "2_2") (pintype "bidirectional"))
      (node (ref "X9") (pin "4") (pinfunction "4_4") (pintype "bidirectional"))
      (node (ref "X9") (pin "6") (pinfunction "6_6") (pintype "bidirectional"))
      (node (ref "X9") (pin "8") (pinfunction "8_8") (pintype "bidirectional"))
      (node (ref "XS5") (pin "3") (pinfunction "3_3") (pintype "passive"))
      (node (ref "XS6") (pin "3") (pinfunction "3_3") (pintype "passive"))
      (node (ref "XS7") (pin "3") (pinfunction "3_3") (pintype "passive"))
      (node (ref "XS8") (pin "3") (pinfunction "3_3") (pintype "passive"))
    )
    (net (code "88") (name "Net-(DS1-A)") (class "Default")
      (node (ref "DS1") (pin "1") (pinfunction "A_1") (pintype "passive"))
      (node (ref "R14") (pin "2") (pinfunction "2_2") (pintype "passive"))
    )
    (net (code "89") (name "Net-(DS1-C)") (class "Default")
      (node (ref "DS1") (pin "2") (pinfunction "C_2") (pintype "passive"))
      (node (ref "VT1") (pin "3") (pinfunction "C_3") (pintype "passive"))
    )
    (net (code "90") (name "Net-(DS2-A)") (class "Default")
      (node (ref "DS2") (pin "1") (pinfunction "A_1") (pintype "passive"))
      (node (ref "R22") (pin "2") (pinfunction "2_2") (pintype "passive"))
    )
    (net (code "91") (name "Net-(DS2-C)") (class "Default")
      (node (ref "DS2") (pin "2") (pinfunction "C_2") (pintype "passive"))
      (node (ref "VT2") (pin "3") (pinfunction "C_3") (pintype "passive"))
    )
    (net (code "92") (name "Net-(DS3-A)") (class "Default")
      (node (ref "DS3") (pin "1") (pinfunction "A_1") (pintype "passive"))
      (node (ref "R24") (pin "2") (pinfunction "2_2") (pintype "passive"))
    )
    (net (code "93") (name "Net-(DS3-C)") (class "Default")
      (node (ref "DS3") (pin "2") (pinfunction "C_2") (pintype "passive"))
      (node (ref "VT3") (pin "3") (pinfunction "C_3") (pintype "passive"))
    )
    (net (code "94") (name "Net-(DS4-A)") (class "Default")
      (node (ref "DS4") (pin "1") (pinfunction "A_1") (pintype "passive"))
      (node (ref "R31") (pin "1") (pinfunction "1_1") (pintype "passive"))
    )
    (net (code "95") (name "Net-(DS5-A)") (class "Default")
      (node (ref "DS5") (pin "1") (pinfunction "A_1") (pintype "passive"))
      (node (ref "R34") (pin "1") (pinfunction "1_1") (pintype "passive"))
    )
    (net (code "96") (name "Net-(DS6-A)") (class "Default")
      (node (ref "DS6") (pin "1") (pinfunction "A_1") (pintype "passive"))
      (node (ref "R37") (pin "1") (pinfunction "1_1") (pintype "passive"))
    )
    (net (code "97") (name "Net-(DS7-A)") (class "Default")
      (node (ref "DS7") (pin "1") (pinfunction "A_1") (pintype "passive"))
      (node (ref "R40") (pin "1") (pinfunction "1_1") (pintype "passive"))
    )
    (net (code "98") (name "Net-(R27-Pad2)") (class "Default")
      (node (ref "R27") (pin "2") (pinfunction "2_2") (pintype "passive"))
      (node (ref "S2") (pin "1") (pinfunction "1_1") (pintype "passive"))
    )
    (net (code "99") (name "Net-(R28-Pad2)") (class "Default")
      (node (ref "R28") (pin "2") (pinfunction "2_2") (pintype "passive"))
      (node (ref "S2") (pin "2") (pinfunction "2_2") (pintype "passive"))
    )
    (net (code "100") (name "Net-(S1-COMMON)") (class "Default")
      (node (ref "R26") (pin "1") (pinfunction "1_1") (pintype "passive"))
      (node (ref "S1") (pin "1") (pinfunction "COMMON_1") (pintype "passive"))
    )
    (net (code "101") (name "Net-(U8-A)") (class "Default")
      (node (ref "R15") (pin "1") (pinfunction "1_1") (pintype "passive"))
      (node (ref "U8") (pin "2") (pinfunction "A_2") (pintype "passive"))
    )
    (net (code "102") (name "Net-(U8-Vo)") (class "Default")
      (node (ref "R20") (pin "1") (pinfunction "1_1") (pintype "passive"))
      (node (ref "U8") (pin "6") (pinfunction "Vo_6") (pintype "output"))
      (node (ref "U9") (pin "2") (pinfunction "~{RE}_2") (pintype "input"))
      (node (ref "U9") (pin "3") (pinfunction "DE_3") (pintype "input"))
    )
    (net (code "103") (name "Net-(U10-Vib)") (class "Default")
      (node (ref "U10") (pin "3") (pinfunction "Vib_3") (pintype "input"))
      (node (ref "U9") (pin "1") (pinfunction "RO_1") (pintype "output"))
    )
    (net (code "104") (name "Net-(U10-Voa)") (class "Default")
      (node (ref "U10") (pin "2") (pinfunction "Voa_2") (pintype "output"))
      (node (ref "U9") (pin "4") (pinfunction "DI_4") (pintype "input"))
    )
    (net (code "105") (name "Net-(U13-A)") (class "Default")
      (node (ref "C21") (pin "1") (pinfunction "1_1") (pintype "passive"))
      (node (ref "R30") (pin "1") (pinfunction "1_1") (pintype "passive"))
      (node (ref "U13") (pin "1") (pinfunction "A_1") (pintype "passive"))
    )
    (net (code "106") (name "Net-(U14-A)") (class "Default")
      (node (ref "C23") (pin "1") (pinfunction "1_1") (pintype "passive"))
      (node (ref "R33") (pin "1") (pinfunction "1_1") (pintype "passive"))
      (node (ref "U14") (pin "1") (pinfunction "A_1") (pintype "passive"))
    )
    (net (code "107") (name "Net-(U15-C1+)") (class "Default")
      (node (ref "C24") (pin "1") (pinfunction "1_1") (pintype "passive"))
      (node (ref "U15") (pin "1") (pinfunction "C1+_1") (pintype "passive"))
    )
    (net (code "108") (name "Net-(U15-C1-)") (class "Default")
      (node (ref "C24") (pin "2") (pinfunction "2_2") (pintype "passive"))
      (node (ref "U15") (pin "3") (pinfunction "C1-_3") (pintype "passive"))
    )
    (net (code "109") (name "Net-(U15-C2+)") (class "Default")
      (node (ref "C26") (pin "1") (pinfunction "1_1") (pintype "passive"))
      (node (ref "U15") (pin "4") (pinfunction "C2+_4") (pintype "passive"))
    )
    (net (code "110") (name "Net-(U15-C2-)") (class "Default")
      (node (ref "C26") (pin "2") (pinfunction "2_2") (pintype "passive"))
      (node (ref "U15") (pin "5") (pinfunction "C2-_5") (pintype "passive"))
    )
    (net (code "111") (name "Net-(U15-V+)") (class "Default")
      (node (ref "C25") (pin "2") (pinfunction "2_2") (pintype "passive"))
      (node (ref "U15") (pin "2") (pinfunction "V+_2") (pintype "power_in"))
    )
    (net (code "112") (name "Net-(U15-V-)") (class "Default")
      (node (ref "C29") (pin "2") (pinfunction "2_2") (pintype "passive"))
      (node (ref "U15") (pin "6") (pinfunction "V-_6") (pintype "power_in"))
    )
    (net (code "113") (name "Net-(U16A-PF0-OSC_IN(PF0))") (class "Default")
      (node (ref "C31") (pin "2") (pinfunction "2_2") (pintype "passive"))
      (node (ref "U16") (pin "5") (pinfunction "PF0-OSC_IN(PF0)_5") (pintype "bidirectional"))
      (node (ref "ZQ1") (pin "2") (pinfunction "OSC2_2") (pintype "passive"))
    )
    (net (code "114") (name "Net-(U16A-PF1-OSC_OUT(PF1))") (class "Default")
      (node (ref "C32") (pin "2") (pinfunction "2_2") (pintype "passive"))
      (node (ref "U16") (pin "6") (pinfunction "PF1-OSC_OUT(PF1)_6") (pintype "bidirectional"))
      (node (ref "ZQ1") (pin "1") (pinfunction "OSC1_1") (pintype "passive"))
    )
    (net (code "115") (name "Net-(U17-A)") (class "Default")
      (node (ref "C27") (pin "1") (pinfunction "1_1") (pintype "passive"))
      (node (ref "R36") (pin "1") (pinfunction "1_1") (pintype "passive"))
      (node (ref "U17") (pin "1") (pinfunction "A_1") (pintype "passive"))
    )
    (net (code "116") (name "Net-(U18-A)") (class "Default")
      (node (ref "C30") (pin "1") (pinfunction "1_1") (pintype "passive"))
      (node (ref "R39") (pin "1") (pinfunction "1_1") (pintype "passive"))
      (node (ref "U18") (pin "1") (pinfunction "A_1") (pintype "passive"))
    )
    (net (code "117") (name "Net-(U19-A)") (class "Default")
      (node (ref "C33") (pin "1") (pinfunction "1_1") (pintype "passive"))
      (node (ref "R42") (pin "1") (pinfunction "1_1") (pintype "passive"))
      (node (ref "U19") (pin "1") (pinfunction "A_1") (pintype "passive"))
    )
    (net (code "118") (name "Net-(U20-A)") (class "Default")
      (node (ref "C34") (pin "1") (pinfunction "1_1") (pintype "passive"))
      (node (ref "R44") (pin "1") (pinfunction "1_1") (pintype "passive"))
      (node (ref "U20") (pin "1") (pinfunction "A_1") (pintype "passive"))
    )
    (net (code "119") (name "Net-(U21-A)") (class "Default")
      (node (ref "C35") (pin "1") (pinfunction "1_1") (pintype "passive"))
      (node (ref "R47") (pin "1") (pinfunction "1_1") (pintype "passive"))
      (node (ref "U21") (pin "1") (pinfunction "A_1") (pintype "passive"))
    )
    (net (code "120") (name "Net-(U22-A)") (class "Default")
      (node (ref "C37") (pin "1") (pinfunction "1_1") (pintype "passive"))
      (node (ref "R49") (pin "1") (pinfunction "1_1") (pintype "passive"))
      (node (ref "U22") (pin "1") (pinfunction "A_1") (pintype "passive"))
    )
    (net (code "121") (name "Net-(VT1-B)") (class "Default")
      (node (ref "R13") (pin "1") (pinfunction "1_1") (pintype "passive"))
      (node (ref "VT1") (pin "1") (pinfunction "B_1") (pintype "passive"))
    )
    (net (code "122") (name "Net-(VT2-B)") (class "Default")
      (node (ref "R19") (pin "1") (pinfunction "1_1") (pintype "passive"))
      (node (ref "VT2") (pin "1") (pinfunction "B_1") (pintype "passive"))
    )
    (net (code "123") (name "Net-(VT3-B)") (class "Default")
      (node (ref "R23") (pin "1") (pinfunction "1_1") (pintype "passive"))
      (node (ref "VT3") (pin "1") (pinfunction "B_1") (pintype "passive"))
    )
    (net (code "124") (name "unconnected-(P3-Pad3)") (class "Default")
      (node (ref "P3") (pin "3") (pinfunction "3_3") (pintype "passive"))
    )
    (net (code "125") (name "unconnected-(P3-Pad4)") (class "Default")
      (node (ref "P3") (pin "4") (pinfunction "4_4") (pintype "passive"))
    )
    (net (code "126") (name "unconnected-(P3-Pad7)") (class "Default")
      (node (ref "P3") (pin "7") (pinfunction "7_7") (pintype "passive"))
    )
    (net (code "127") (name "unconnected-(P3-Pad8)") (class "Default")
      (node (ref "P3") (pin "8") (pinfunction "8_8") (pintype "passive"))
    )
    (net (code "128") (name "unconnected-(P3-Pad9)") (class "Default")
      (node (ref "P3") (pin "9") (pinfunction "9_9") (pintype "passive"))
    )
    (net (code "129") (name "unconnected-(P3-Pad10)") (class "Default")
      (node (ref "P3") (pin "10") (pinfunction "10_10") (pintype "passive"))
    )
    (net (code "130") (name "unconnected-(U8-NC-Pad1)") (class "Default")
      (node (ref "U8") (pin "1") (pinfunction "NC_1") (pintype "passive"))
    )
    (net (code "131") (name "unconnected-(U8-NC-Pad4)") (class "Default")
      (node (ref "U8") (pin "4") (pinfunction "NC_4") (pintype "passive"))
    )
    (net (code "132") (name "unconnected-(U15-R2IN-Pad8)") (class "Default")
      (node (ref "U15") (pin "8") (pinfunction "R2IN_8") (pintype "input"))
    )
    (net (code "133") (name "unconnected-(U15-R2OUT-Pad9)") (class "Default")
      (node (ref "U15") (pin "9") (pinfunction "R2OUT_9") (pintype "output"))
    )
    (net (code "134") (name "unconnected-(U15-T2IN-Pad10)") (class "Default")
      (node (ref "U15") (pin "10") (pinfunction "T2IN_10") (pintype "input"))
    )
    (net (code "135") (name "unconnected-(U15-T2OUT-Pad7)") (class "Default")
      (node (ref "U15") (pin "7") (pinfunction "T2OUT_7") (pintype "output"))
    )
    (net (code "136") (name "unconnected-(U16A-PA1-Pad15)") (class "Default")
      (node (ref "U16") (pin "15") (pinfunction "PA1_15") (pintype "bidirectional"))
    )
    (net (code "137") (name "unconnected-(U16A-PA2-Pad16)") (class "Default")
      (node (ref "U16") (pin "16") (pinfunction "PA2_16") (pintype "bidirectional"))
    )
    (net (code "138") (name "unconnected-(U16A-PA3-Pad17)") (class "Default")
      (node (ref "U16") (pin "17") (pinfunction "PA3_17") (pintype "bidirectional"))
    )
    (net (code "139") (name "unconnected-(U16A-PA4-Pad20)") (class "Default")
      (node (ref "U16") (pin "20") (pinfunction "PA4_20") (pintype "bidirectional"))
    )
    (net (code "140") (name "unconnected-(U16A-PA11-Pad44)") (class "Default")
      (node (ref "U16") (pin "44") (pinfunction "PA11_44") (pintype "bidirectional"))
    )
    (net (code "141") (name "unconnected-(U16A-PA12-Pad45)") (class "Default")
      (node (ref "U16") (pin "45") (pinfunction "PA12_45") (pintype "bidirectional"))
    )
    (net (code "142") (name "unconnected-(U16A-PC13-Pad2)") (class "Default")
      (node (ref "U16") (pin "2") (pinfunction "PC13_2") (pintype "bidirectional"))
    )
    (net (code "143") (name "unconnected-(U16A-PC14-OSC32_IN(PC14)-Pad3)") (class "Default")
      (node (ref "U16") (pin "3") (pinfunction "PC14-OSC32_IN(PC14)_3") (pintype "bidirectional"))
    )
    (net (code "144") (name "unconnected-(U16A-PC15-OSC32_OUT(PC15)-Pad4)") (class "Default")
      (node (ref "U16") (pin "4") (pinfunction "PC15-OSC32_OUT(PC15)_4") (pintype "bidirectional"))
    )
    (net (code "145") (name "unconnected-(XS1-Pad1)") (class "Default")
      (node (ref "XS1") (pin "1") (pinfunction "1_1") (pintype "passive"))
    )
    (net (code "146") (name "unconnected-(XS2-Pad1)") (class "Default")
      (node (ref "XS2") (pin "1") (pinfunction "1_1") (pintype "passive"))
    )
    (net (code "147") (name "unconnected-(XS4-Pad1)") (class "Default")
      (node (ref "XS4") (pin "1") (pinfunction "1_1") (pintype "passive"))
    )
    (net (code "148") (name "unconnected-(XS4-SH-Pad13)") (class "Default")
      (node (ref "XS4") (pin "13") (pinfunction "SH_13") (pintype "passive"))
    )
    (net (code "149") (name "unconnected-(XS5-Pad4)") (class "Default")
      (node (ref "XS5") (pin "4") (pinfunction "4_4") (pintype "passive"))
    )
    (net (code "150") (name "unconnected-(XS6-Pad4)") (class "Default")
      (node (ref "XS6") (pin "4") (pinfunction "4_4") (pintype "passive"))
    )
    (net (code "151") (name "unconnected-(XS7-Pad4)") (class "Default")
      (node (ref "XS7") (pin "4") (pinfunction "4_4") (pintype "passive"))
    )
    (net (code "152") (name "unconnected-(XS8-Pad4)") (class "Default")
      (node (ref "XS8") (pin "4") (pinfunction "4_4") (pintype "passive"))
    )
  )
)
